# 3_amplifier.net
KiCad netlist of a schematic drawn in Altium Designer
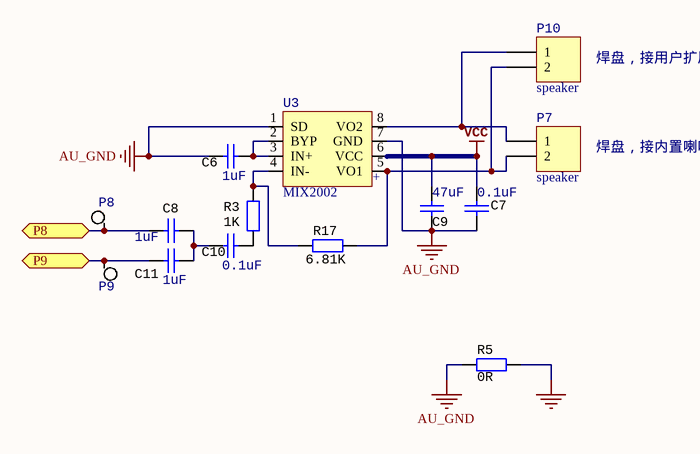
[diagram p0: 3 amplifier.SchDoc]

(export (version "E")
  (design (tool "Eeschema 10.0.6"))
  (components
    (comp (ref "C6")
      (value "1uF")
      (footprint "0402")
      (description "CAP, CERM, 0.01uF, 100V, +/-5%, X7R, 0603")
      (fields (field (name "PARTNUMBER") "06031C103JAT2A") (field (name "MANUFACTURER") "AVX"))
      (libsource (lib "03.常用器件") (part "CAP1_npol"))
    )
    (comp (ref "C7")
      (value "0.1uF")
      (footprint "0402")
      (description "CAP, CERM, 0.01uF, 100V, +/-5%, X7R, 0603")
      (fields (field (name "PARTNUMBER") "06031C103JAT2A") (field (name "MANUFACTURER") "AVX"))
      (libsource (lib "03.常用器件") (part "CAP1_npol"))
    )
    (comp (ref "C8")
      (value "1uF")
      (footprint "0402")
      (description "CAP, CERM, 0.01uF, 100V, +/-5%, X7R, 0603")
      (fields (field (name "PARTNUMBER") "06031C103JAT2A") (field (name "MANUFACTURER") "AVX"))
      (libsource (lib "03.常用器件") (part "CAP1_npol"))
    )
    (comp (ref "C9")
      (value "47uF")
      (footprint "0805")
      (description "CAP, CERM, 0.01uF, 100V, +/-5%, X7R, 0603")
      (fields (field (name "PARTNUMBER") "06031C103JAT2A") (field (name "MANUFACTURER") "AVX"))
      (libsource (lib "03.常用器件") (part "CAP1_npol"))
    )
    (comp (ref "C10")
      (value "0.1uF")
      (footprint "0402")
      (description "CAP, CERM, 0.01uF, 100V, +/-5%, X7R, 0603")
      (fields (field (name "PARTNUMBER") "06031C103JAT2A") (field (name "MANUFACTURER") "AVX"))
      (libsource (lib "03.常用器件") (part "CAP1_npol"))
    )
    (comp (ref "C11")
      (value "1uF")
      (footprint "0402")
      (description "CAP, CERM, 0.01uF, 100V, +/-5%, X7R, 0603")
      (fields (field (name "PARTNUMBER") "06031C103JAT2A") (field (name "MANUFACTURER") "AVX"))
      (libsource (lib "03.常用器件") (part "CAP1_npol"))
    )
    (comp (ref "P7")
      (value "speaker")
      (footprint "焊盘")
      (description "Header, 2-Pin")
      (fields (field (name "PUBLISHER") "Altium Limited"))
      (libsource (lib "Miscellaneous Connectors") (part "Header 2"))
    )
    (comp (ref "P8")
      (value "~")
      (footprint "测试点")
      (description "Test Point")
      (libsource (lib "my_Schlib") (part "TP"))
    )
    (comp (ref "P9")
      (value "~")
      (footprint "测试点")
      (description "Test Point")
      (libsource (lib "my_Schlib") (part "TP"))
    )
    (comp (ref "P10")
      (value "speaker")
      (footprint "2PIN/2.0MM座子")
      (description "Header, 2-Pin")
      (fields (field (name "PUBLISHER") "Altium Limited"))
      (libsource (lib "Miscellaneous Connectors") (part "Header 2"))
    )
    (comp (ref "R3")
      (value "1K")
      (footprint "0402")
      (description "RES, 1.0k ohm, 5%, 0.1W, 0603")
      (fields
        (field (name "PARTNUMBER") "RC0603JR-071KL")
        (field (name "MANUFACTURER") "Yageo America")
        (field (name "PUBLISHER") "Texas Instruments")
      )
      (libsource (lib "") (part "RES1_2"))
    )
    (comp (ref "R5")
      (value "0R")
      (footprint "0402")
      (description "RES, 1.0k ohm, 5%, 0.1W, 0603")
      (fields
        (field (name "PARTNUMBER") "RC0603JR-071KL")
        (field (name "MANUFACTURER") "Yageo America")
        (field (name "PUBLISHER") "Texas Instruments")
      )
      (libsource (lib "") (part "RES1_1"))
    )
    (comp (ref "R17")
      (value "6.81K")
      (footprint "0402")
      (description "RES, 1.0k ohm, 5%, 0.1W, 0603")
      (fields
        (field (name "PARTNUMBER") "RC0603JR-071KL")
        (field (name "MANUFACTURER") "Yageo America")
        (field (name "PUBLISHER") "Texas Instruments")
      )
      (libsource (lib "03.常用器件") (part "RES1"))
    )
    (comp (ref "U3") (value "MIX2002") (footprint "SOP-8") (libsource (lib "Schlib1") (part "MIX2002")))
  )
  (nets
    (net (code "1") (name "/P8") (class "Default")
      (node (ref "C8") (pin "2") (pinfunction "2_2") (pintype "passive"))
      (node (ref "P8") (pin "1") (pinfunction "1_1") (pintype "passive"))
    )
    (net (code "2") (name "/P9") (class "Default")
      (node (ref "C11") (pin "2") (pinfunction "2_2") (pintype "passive"))
      (node (ref "P9") (pin "1") (pinfunction "1_1") (pintype "passive"))
    )
    (net (code "3") (name "<NO NET>") (class "Default")
      (node (ref "R5") (pin "1") (pinfunction "1_1") (pintype "passive"))
    )
    (net (code "4") (name "AU_GND") (class "Default")
      (node (ref "C6") (pin "1") (pinfunction "1_1") (pintype "passive"))
      (node (ref "C7") (pin "2") (pinfunction "2_2") (pintype "passive"))
      (node (ref "C9") (pin "2") (pinfunction "2_2") (pintype "passive"))
      (node (ref "R5") (pin "2") (pinfunction "2_2") (pintype "passive"))
      (node (ref "U3") (pin "1") (pinfunction "SD_1") (pintype "passive"))
      (node (ref "U3") (pin "7") (pinfunction "GND_7") (pintype "passive"))
    )
    (net (code "5") (name "Net-(C10-Pad1)") (class "Default")
      (node (ref "C10") (pin "1") (pinfunction "1_1") (pintype "passive"))
      (node (ref "C11") (pin "1") (pinfunction "1_1") (pintype "passive"))
      (node (ref "C8") (pin "1") (pinfunction "1_1") (pintype "passive"))
    )
    (net (code "6") (name "Net-(C10-Pad2)") (class "Default")
      (node (ref "C10") (pin "2") (pinfunction "2_2") (pintype "passive"))
      (node (ref "R3") (pin "1") (pinfunction "1_1") (pintype "passive"))
    )
    (net (code "7") (name "Net-(U3-BYP)") (class "Default")
      (node (ref "C6") (pin "2") (pinfunction "2_2") (pintype "passive"))
      (node (ref "U3") (pin "2") (pinfunction "BYP_2") (pintype "passive"))
      (node (ref "U3") (pin "3") (pinfunction "IN+_3") (pintype "passive"))
    )
    (net (code "8") (name "Net-(U3-IN-)") (class "Default")
      (node (ref "R17") (pin "1") (pinfunction "1_1") (pintype "passive"))
      (node (ref "R3") (pin "2") (pinfunction "2_2") (pintype "passive"))
      (node (ref "U3") (pin "4") (pinfunction "IN-_4") (pintype "passive"))
    )
    (net (code "9") (name "Net-(U3-VO1)") (class "Default")
      (node (ref "P10") (pin "2") (pinfunction "2_2") (pintype "passive"))
      (node (ref "P7") (pin "2") (pinfunction "2_2") (pintype "passive"))
      (node (ref "R17") (pin "2") (pinfunction "2_2") (pintype "passive"))
      (node (ref "U3") (pin "5") (pinfunction "VO1_5") (pintype "passive"))
    )
    (net (code "10") (name "Net-(U3-VO2)") (class "Default")
      (node (ref "P10") (pin "1") (pinfunction "1_1") (pintype "passive"))
      (node (ref "P7") (pin "1") (pinfunction "1_1") (pintype "passive"))
      (node (ref "U3") (pin "8") (pinfunction "VO2_8") (pintype "passive"))
    )
    (net (code "11") (name "VCC") (class "Default")
      (node (ref "C7") (pin "1") (pinfunction "1_1") (pintype "passive"))
      (node (ref "C9") (pin "1") (pinfunction "1_1") (pintype "passive"))
      (node (ref "U3") (pin "6") (pinfunction "VCC_6") (pintype "passive"))
    )
  )
)
